# eeZeeISP3.net
KiCad netlist of a schematic drawn in EAGLE
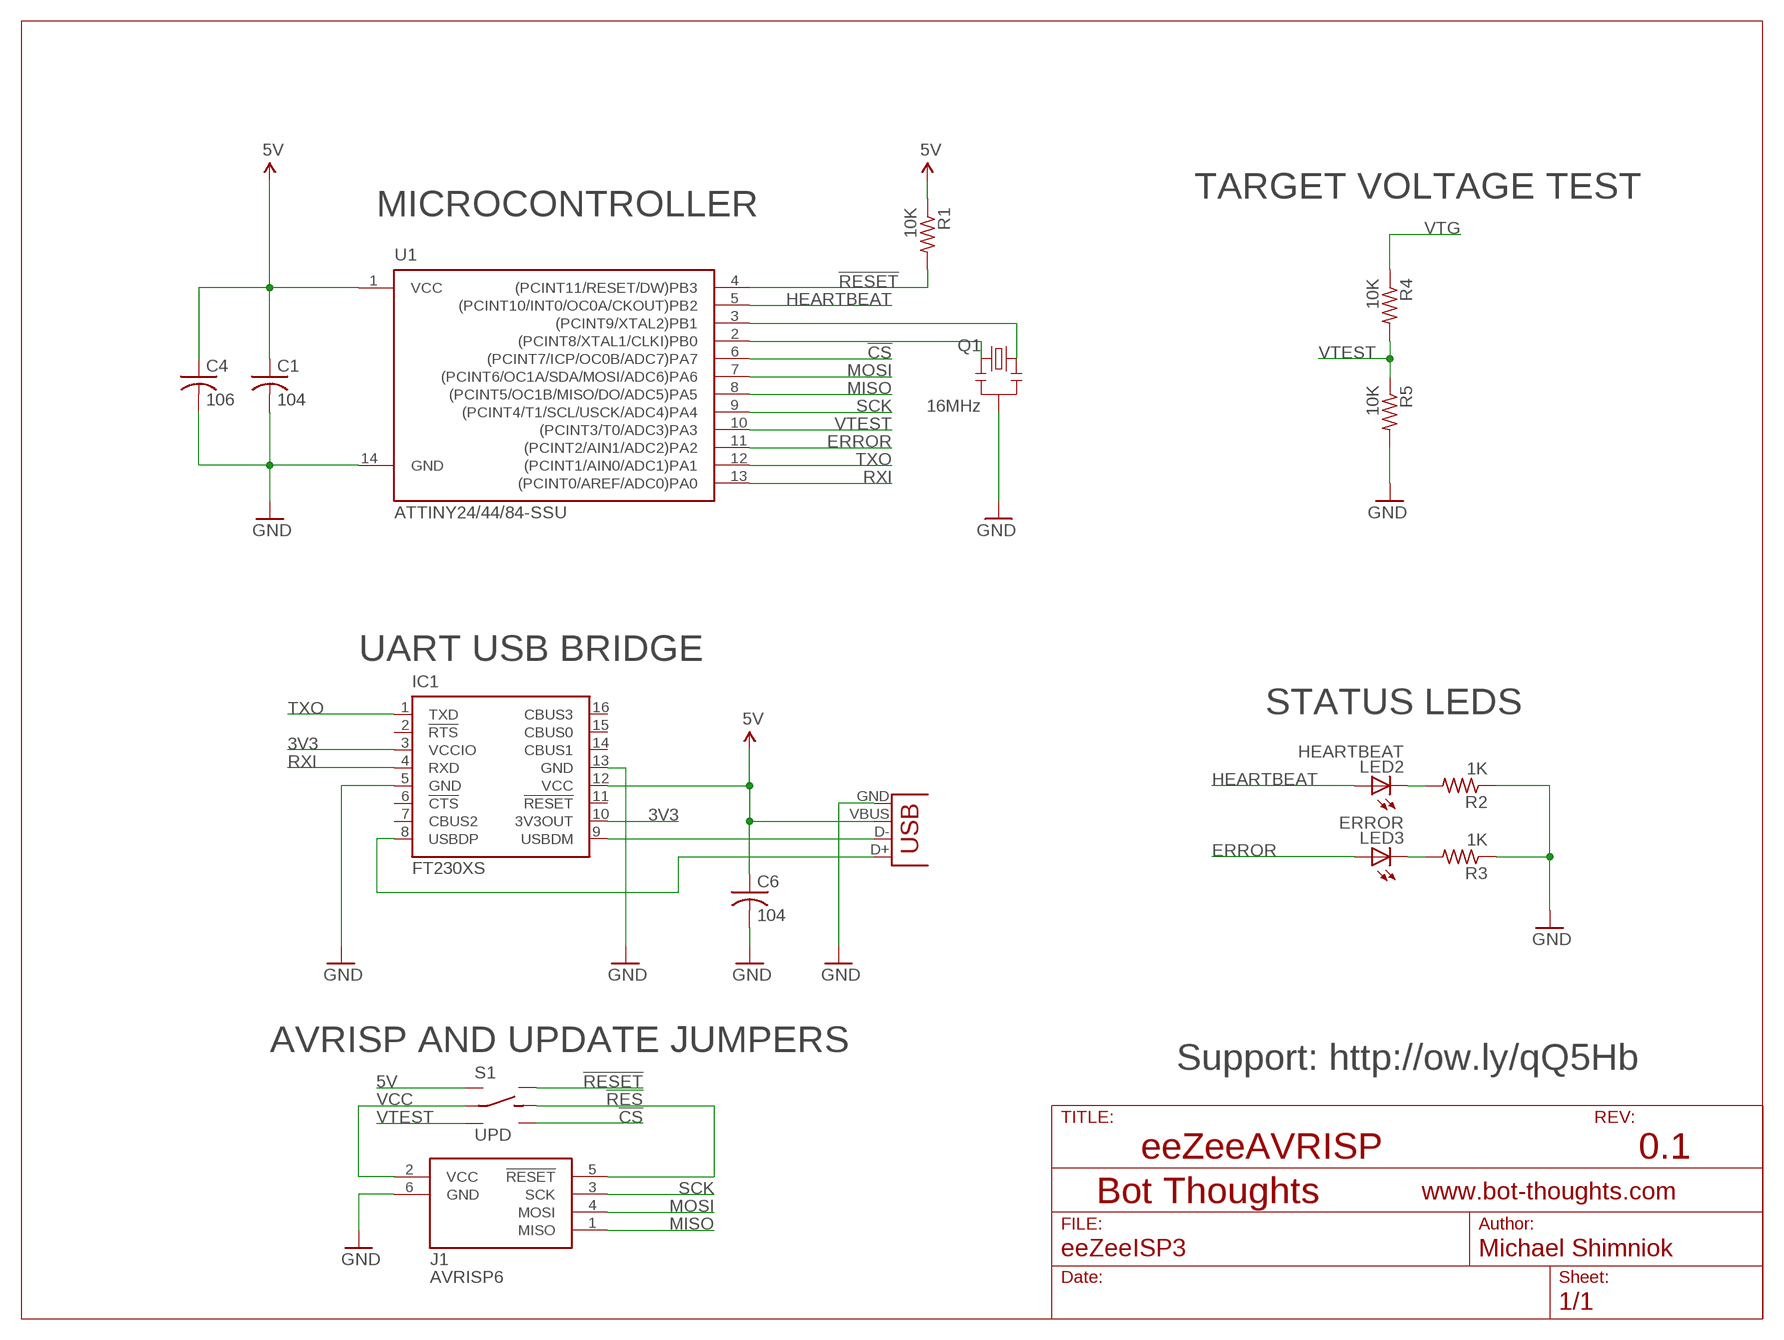
[diagram p0: schematic, sheet 1]

(export (version "E")
  (design (tool "Eeschema 10.0.6"))
  (components
    (comp (ref "C1")
      (value "104")
      (footprint "eagle-import:C0603")
      (libsource (lib "eagle-import") (part "C-USC0603"))
    )
    (comp (ref "C4")
      (value "106")
      (footprint "eagle-import:C0603")
      (libsource (lib "eagle-import") (part "C-USC0603"))
    )
    (comp (ref "C6")
      (value "104")
      (footprint "eagle-import:C0603")
      (libsource (lib "eagle-import") (part "C-USC0603"))
    )
    (comp (ref "IC1")
      (value "FT230XS")
      (footprint "eagle-import:SSOP16")
      (libsource (lib "eagle-import") (part "FT230XS"))
    )
    (comp (ref "J1")
      (value "AVRISP6")
      (footprint "eagle-import:CON6P2R")
      (libsource (lib "eagle-import") (part "AVRISP6"))
    )
    (comp (ref "LED2")
      (value "HEARTBEAT")
      (footprint "eagle-import:CHIPLED_1206")
      (libsource (lib "eagle-import") (part "LEDCHIPLED_1206"))
    )
    (comp (ref "LED3")
      (value "ERROR")
      (footprint "eagle-import:CHIPLED_1206")
      (libsource (lib "eagle-import") (part "LEDCHIPLED_1206"))
    )
    (comp (ref "Q1")
      (value "16MHz")
      (footprint "eagle-import:CSTCE_V_C")
      (libsource (lib "eagle-import") (part "RESONATOR_CSTCE_V_C"))
    )
    (comp (ref "R1")
      (value "10K")
      (footprint "eagle-import:R0603")
      (libsource (lib "eagle-import") (part "R-US_R0603"))
    )
    (comp (ref "R2")
      (value "1K")
      (footprint "eagle-import:R0603")
      (libsource (lib "eagle-import") (part "R-US_R0603"))
    )
    (comp (ref "R3")
      (value "1K")
      (footprint "eagle-import:R0603")
      (libsource (lib "eagle-import") (part "R-US_R0603"))
    )
    (comp (ref "R4")
      (value "10K")
      (footprint "eagle-import:R0603")
      (libsource (lib "eagle-import") (part "R-US_R0603"))
    )
    (comp (ref "R5")
      (value "10K")
      (footprint "eagle-import:R0603")
      (libsource (lib "eagle-import") (part "R-US_R0603"))
    )
    (comp (ref "S1")
      (value "UPD")
      (footprint "eagle-import:DPDT_JS202011CQN")
      (libsource (lib "eagle-import") (part "DPDT_JS202011CQN"))
    )
    (comp (ref "U1")
      (value "ATTINY24/44/84-SSU")
      (footprint "eagle-import:SOIC14")
      (libsource (lib "eagle-import") (part "ATTINY24/44/84-SSU"))
    )
    (comp (ref "X2")
      (value "USB-SMD-NS")
      (footprint "eagle-import:USB-MINIB-NOSTOP")
      (libsource (lib "eagle-import") (part "USB-SMD-NS"))
    )
  )
  (nets
    (net (code "1") (name "/3V3") (class "Default")
      (node (ref "IC1") (pin "10") (pinfunction "3V3OUT_10") (pintype "output"))
      (node (ref "IC1") (pin "3") (pinfunction "VCCIO_3") (pintype "power_in"))
    )
    (net (code "2") (name "/ERROR") (class "Default")
      (node (ref "LED3") (pin "A") (pinfunction "A_A") (pintype "passive"))
      (node (ref "U1") (pin "11") (pinfunction "(PCINT2/AIN1/ADC2)PA2_11") (pintype "bidirectional"))
    )
    (net (code "3") (name "/HEARTBEAT") (class "Default")
      (node (ref "LED2") (pin "A") (pinfunction "A_A") (pintype "passive"))
      (node (ref "U1") (pin "5") (pinfunction "(PCINT10/INT0/OC0A/CKOUT)PB2_5") (pintype "bidirectional"))
    )
    (net (code "4") (name "/MISO") (class "Default")
      (node (ref "J1") (pin "1") (pinfunction "MISO_1") (pintype "input"))
      (node (ref "U1") (pin "8") (pinfunction "(PCINT5/OC1B/MISO/DO/ADC5)PA5_8") (pintype "bidirectional"))
    )
    (net (code "5") (name "/MOSI") (class "Default")
      (node (ref "J1") (pin "4") (pinfunction "MOSI_4") (pintype "output"))
      (node (ref "U1") (pin "7") (pinfunction "(PCINT6/OC1A/SDA/MOSI/ADC6)PA6_7") (pintype "bidirectional"))
    )
    (net (code "6") (name "/RXI") (class "Default")
      (node (ref "IC1") (pin "4") (pinfunction "RXD_4") (pintype "input"))
      (node (ref "U1") (pin "13") (pinfunction "(PCINT0/AREF/ADC0)PA0_13") (pintype "bidirectional"))
    )
    (net (code "7") (name "/SCK") (class "Default")
      (node (ref "J1") (pin "3") (pinfunction "SCK_3") (pintype "output"))
      (node (ref "U1") (pin "9") (pinfunction "(PCINT4/T1/SCL/USCK/ADC4)PA4_9") (pintype "bidirectional"))
    )
    (net (code "8") (name "/TXO") (class "Default")
      (node (ref "IC1") (pin "1") (pinfunction "TXD_1") (pintype "output"))
      (node (ref "U1") (pin "12") (pinfunction "(PCINT1/AIN0/ADC1)PA1_12") (pintype "bidirectional"))
    )
    (net (code "9") (name "/VCC") (class "Default")
      (node (ref "J1") (pin "2") (pinfunction "VCC_2") (pintype "power_in"))
      (node (ref "S1") (pin "2") (pinfunction "LC_2") (pintype "passive"))
    )
    (net (code "10") (name "/VTEST") (class "Default")
      (node (ref "R4") (pin "2") (pinfunction "2_2") (pintype "passive"))
      (node (ref "R5") (pin "1") (pinfunction "1_1") (pintype "passive"))
      (node (ref "S1") (pin "3") (pinfunction "L2_3") (pintype "passive"))
      (node (ref "U1") (pin "10") (pinfunction "(PCINT3/T0/ADC3)PA3_10") (pintype "bidirectional"))
    )
    (net (code "11") (name "/VTG") (class "Default")
      (node (ref "R4") (pin "1") (pinfunction "1_1") (pintype "passive"))
    )
    (net (code "12") (name "/~{CS}") (class "Default")
      (node (ref "S1") (pin "6") (pinfunction "R2_6") (pintype "passive"))
      (node (ref "U1") (pin "6") (pinfunction "(PCINT7/ICP/OC0B/ADC7)PA7_6") (pintype "bidirectional"))
    )
    (net (code "13") (name "/~{RESET}") (class "Default")
      (node (ref "R1") (pin "2") (pinfunction "2_2") (pintype "passive"))
      (node (ref "S1") (pin "4") (pinfunction "R1_4") (pintype "passive"))
      (node (ref "U1") (pin "4") (pinfunction "(PCINT11/RESET/DW)PB3_4") (pintype "bidirectional"))
    )
    (net (code "14") (name "/~{RES}") (class "Default")
      (node (ref "J1") (pin "5") (pinfunction "~{RESET}_5") (pintype "output"))
      (node (ref "S1") (pin "5") (pinfunction "RC_5") (pintype "passive"))
    )
    (net (code "15") (name "5V") (class "Default")
      (node (ref "C1") (pin "1") (pinfunction "1_1") (pintype "passive"))
      (node (ref "C4") (pin "1") (pinfunction "1_1") (pintype "passive"))
      (node (ref "C6") (pin "1") (pinfunction "1_1") (pintype "passive"))
      (node (ref "IC1") (pin "12") (pinfunction "VCC_12") (pintype "power_in"))
      (node (ref "R1") (pin "1") (pinfunction "1_1") (pintype "passive"))
      (node (ref "S1") (pin "1") (pinfunction "L1_1") (pintype "passive"))
      (node (ref "U1") (pin "1") (pinfunction "VCC_1") (pintype "bidirectional"))
      (node (ref "X2") (pin "VBUS") (pinfunction "VBUS_VBUS") (pintype "bidirectional"))
    )
    (net (code "16") (name "GND") (class "Default")
      (node (ref "C1") (pin "2") (pinfunction "2_2") (pintype "passive"))
      (node (ref "C4") (pin "2") (pinfunction "2_2") (pintype "passive"))
      (node (ref "C6") (pin "2") (pinfunction "2_2") (pintype "passive"))
      (node (ref "IC1") (pin "13") (pinfunction "GND_13") (pintype "power_in"))
      (node (ref "IC1") (pin "5") (pinfunction "GND_5") (pintype "power_in"))
      (node (ref "J1") (pin "6") (pinfunction "GND_6") (pintype "power_in"))
      (node (ref "Q1") (pin "GND") (pinfunction "GND_GND") (pintype "passive"))
      (node (ref "R2") (pin "1") (pinfunction "1_1") (pintype "passive"))
      (node (ref "R3") (pin "1") (pinfunction "1_1") (pintype "passive"))
      (node (ref "R5") (pin "2") (pinfunction "2_2") (pintype "passive"))
      (node (ref "U1") (pin "14") (pinfunction "GND_14") (pintype "bidirectional"))
      (node (ref "X2") (pin "GND") (pinfunction "GND_GND") (pintype "bidirectional"))
    )
    (net (code "17") (name "Net-(IC1-USBDM)") (class "Default")
      (node (ref "IC1") (pin "9") (pinfunction "USBDM_9") (pintype "input"))
      (node (ref "X2") (pin "D-") (pinfunction "D-_D-") (pintype "bidirectional"))
    )
    (net (code "18") (name "Net-(IC1-USBDP)") (class "Default")
      (node (ref "IC1") (pin "8") (pinfunction "USBDP_8") (pintype "input"))
      (node (ref "X2") (pin "D+") (pinfunction "D+_D+") (pintype "bidirectional"))
    )
    (net (code "19") (name "Net-(LED2-PadC)") (class "Default")
      (node (ref "LED2") (pin "C") (pinfunction "C_C") (pintype "passive"))
      (node (ref "R2") (pin "2") (pinfunction "2_2") (pintype "passive"))
    )
    (net (code "20") (name "Net-(LED3-PadC)") (class "Default")
      (node (ref "LED3") (pin "C") (pinfunction "C_C") (pintype "passive"))
      (node (ref "R3") (pin "2") (pinfunction "2_2") (pintype "passive"))
    )
    (net (code "21") (name "Net-(U1-(PCINT8{slash}XTAL1{slash}CLKI)PB0)") (class "Default")
      (node (ref "Q1") (pin "X2") (pinfunction "X2_X2") (pintype "passive"))
      (node (ref "U1") (pin "2") (pinfunction "(PCINT8/XTAL1/CLKI)PB0_2") (pintype "bidirectional"))
    )
    (net (code "22") (name "Net-(U1-(PCINT9{slash}XTAL2)PB1)") (class "Default")
      (node (ref "Q1") (pin "X1") (pinfunction "X1_X1") (pintype "passive"))
      (node (ref "U1") (pin "3") (pinfunction "(PCINT9/XTAL2)PB1_3") (pintype "bidirectional"))
    )
    (net (code "23") (name "unconnected-(IC1-CBUS0-Pad15)") (class "Default")
      (node (ref "IC1") (pin "15") (pinfunction "CBUS0_15") (pintype "bidirectional"))
    )
    (net (code "24") (name "unconnected-(IC1-CBUS1-Pad14)") (class "Default")
      (node (ref "IC1") (pin "14") (pinfunction "CBUS1_14") (pintype "bidirectional"))
    )
    (net (code "25") (name "unconnected-(IC1-CBUS2-Pad7)") (class "Default")
      (node (ref "IC1") (pin "7") (pinfunction "CBUS2_7") (pintype "bidirectional"))
    )
    (net (code "26") (name "unconnected-(IC1-CBUS3-Pad16)") (class "Default")
      (node (ref "IC1") (pin "16") (pinfunction "CBUS3_16") (pintype "bidirectional"))
    )
    (net (code "27") (name "unconnected-(IC1-~{CTS}-Pad6)") (class "Default")
      (node (ref "IC1") (pin "6") (pinfunction "~{CTS}_6") (pintype "input"))
    )
    (net (code "28") (name "unconnected-(IC1-~{RESET}-Pad11)") (class "Default")
      (node (ref "IC1") (pin "11") (pinfunction "~{RESET}_11") (pintype "input"))
    )
    (net (code "29") (name "unconnected-(IC1-~{RTS}-Pad2)") (class "Default")
      (node (ref "IC1") (pin "2") (pinfunction "~{RTS}_2") (pintype "output"))
    )
  )
)
